# LMAT_AMT_MAG__V1.net
KiCad netlist of a schematic drawn in Altium Designer
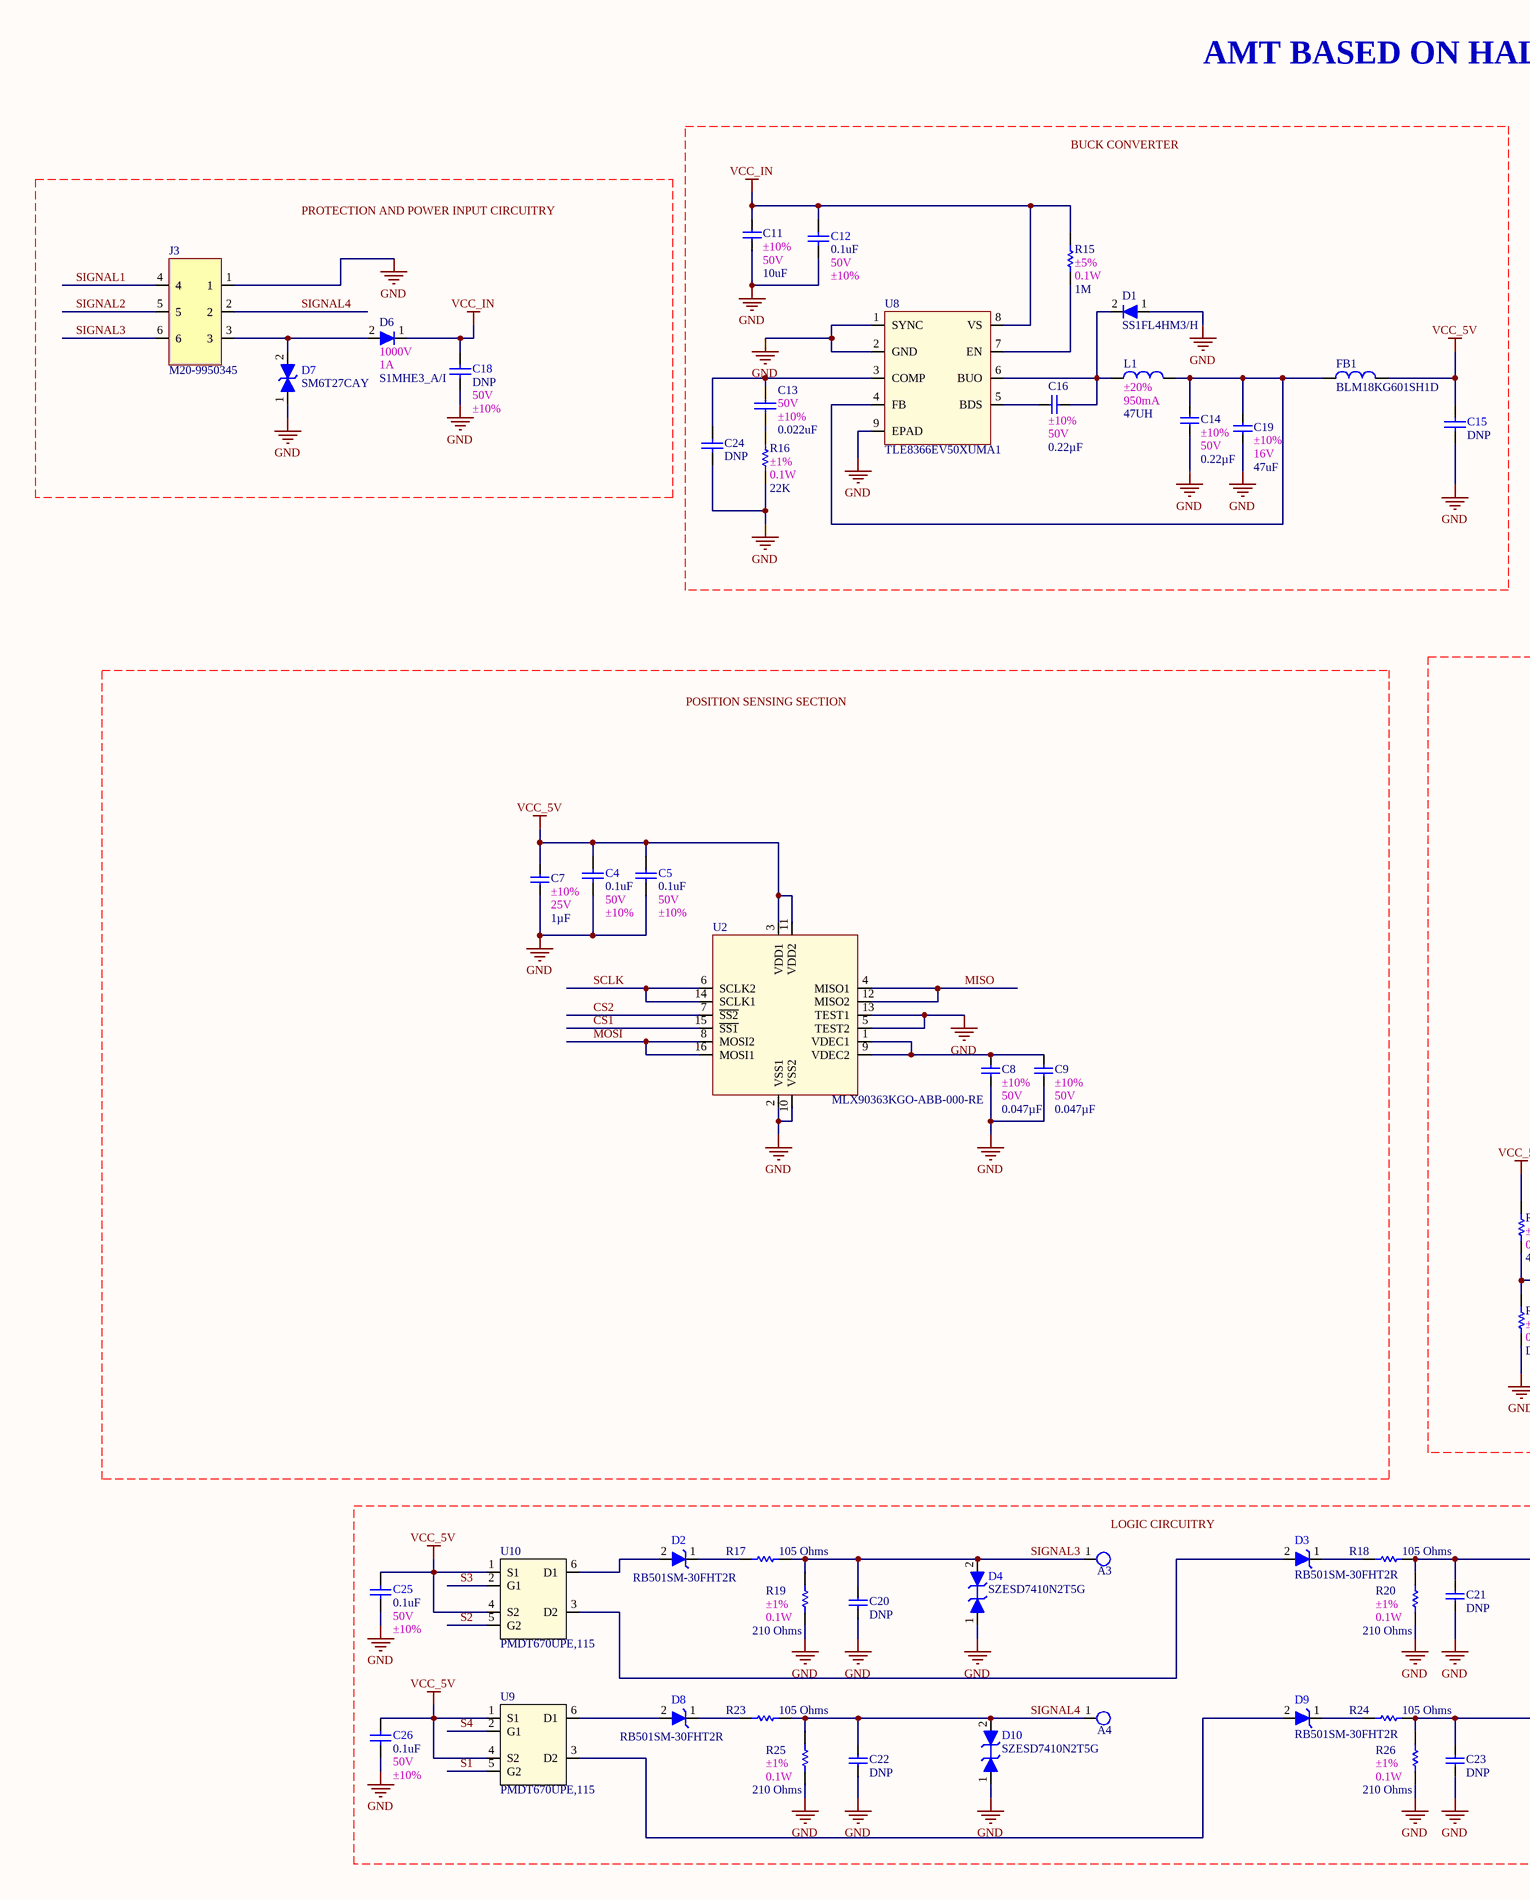
[diagram p0: LMAT_AMT_MAG__V1.SchDoc, left]
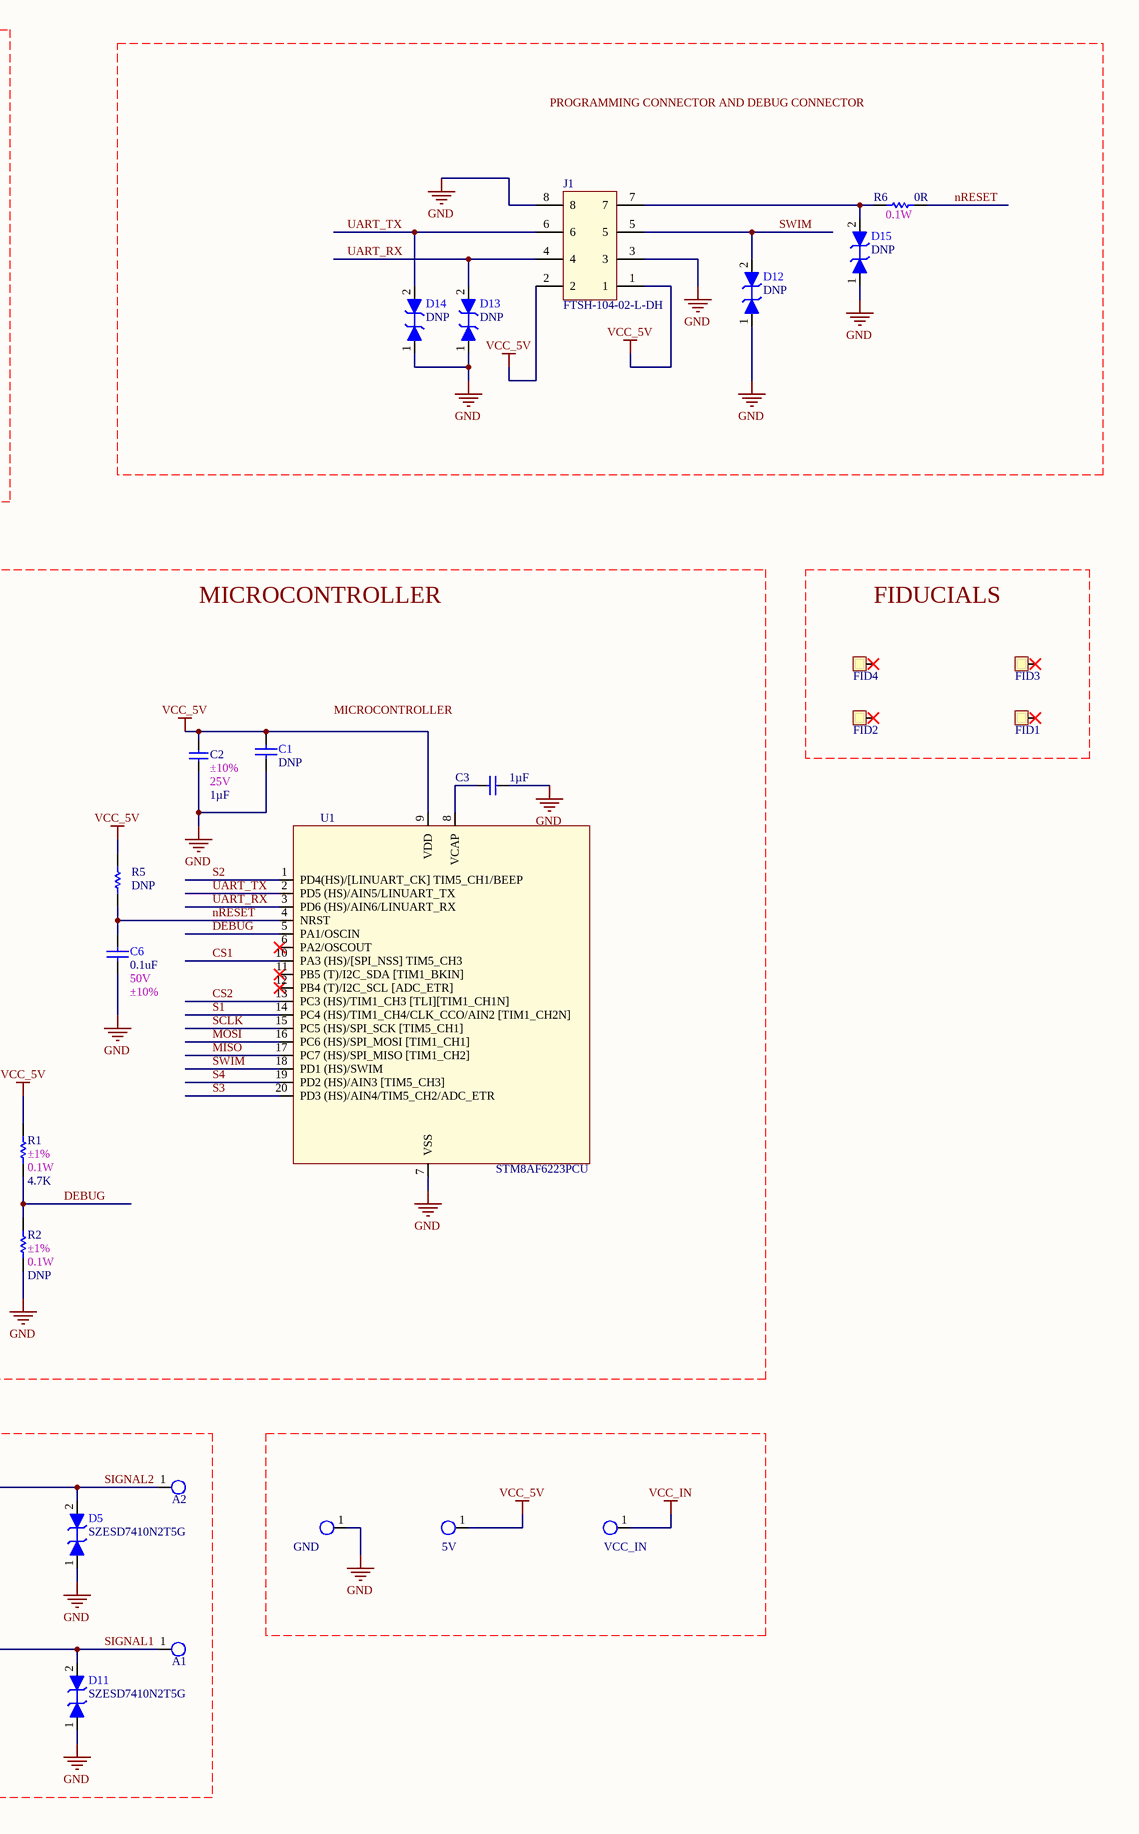
[diagram p1: LMAT_AMT_MAG__V1.SchDoc, right]

(export (version "E")
  (design (tool "Eeschema 10.0.6"))
  (components
    (comp (ref "5V")
      (value "Test Point- 35mil")
      (footprint "TP_35M_DIA")
      (fields (field (name "INTERNAL PART NUMBER") "EMS-TP35MIL-S"))
      (libsource (lib "Integrated_Master_Library") (part "EMS-TP35MIL-S"))
    )
    (comp (ref "A1")
      (value "Test Point- 35mil")
      (footprint "TP_35M_DIA")
      (fields (field (name "INTERNAL PART NUMBER") "EMS-TP35MIL-S"))
      (libsource (lib "Integrated_Master_Library") (part "EMS-TP35MIL-S"))
    )
    (comp (ref "A2")
      (value "Test Point- 35mil")
      (footprint "TP_35M_DIA")
      (fields (field (name "INTERNAL PART NUMBER") "EMS-TP35MIL-S"))
      (libsource (lib "Integrated_Master_Library") (part "EMS-TP35MIL-S"))
    )
    (comp (ref "A3")
      (value "Test Point- 35mil")
      (footprint "TP_35M_DIA")
      (fields (field (name "INTERNAL PART NUMBER") "EMS-TP35MIL-S"))
      (libsource (lib "Integrated_Master_Library") (part "EMS-TP35MIL-S"))
    )
    (comp (ref "A4")
      (value "Test Point- 35mil")
      (footprint "TP_35M_DIA")
      (fields (field (name "INTERNAL PART NUMBER") "EMS-TP35MIL-S"))
      (libsource (lib "Integrated_Master_Library") (part "EMS-TP35MIL-S"))
    )
    (comp (ref "C1")
      (value "DNP")
      (footprint "SMDC0603")
      (description "CAP CER 0.1UF 50V 10% X7R 0603")
      (fields
        (field (name "MANUFACTURER PART NUMBER") "CGA3E2X7R1H104K080AA")
        (field (name "MANUFACTURER") "TDK Corporation")
      )
      (libsource (lib "Integrated_Master_Library") (part "ECA0U10K50V0-SC"))
    )
    (comp (ref "C2")
      (value "1µF")
      (footprint "SMDC0603")
      (description "CAP CER 1UF 25V X7R 0603")
      (fields
        (field (name "MANUFACTURER") "TDK Corporation")
        (field (name "VENDOR PART NUMBER") "445-173628-1-ND")
        (field (name "2ND AUXILIARY FIELD") "±10%")
        (field (name "1ST AUXILIARY FIELD") "25V")
      )
      (libsource (lib "Integrated_Master_Library (3)") (part "ECA1U00L25V0-SC"))
    )
    (comp (ref "C3")
      (value "1µF")
      (footprint "SMDC0603")
      (description "CAP CER 1UF 25V X7R 0603")
      (fields
        (field (name "MANUFACTURER") "TDK Corporation")
        (field (name "VENDOR PART NUMBER") "445-173628-1-ND")
      )
      (libsource (lib "Integrated_Master_Library (3)") (part "ECA1U00L25V0-SC"))
    )
    (comp (ref "C4")
      (value "0.1uF")
      (footprint "SMDC0603")
      (description "CAP CER 0.1UF 50V 10% X7R 0603")
      (fields
        (field (name "MANUFACTURER PART NUMBER") "CGA3E2X7R1H104K080AA")
        (field (name "MANUFACTURER") "TDK Corporation")
        (field (name "1ST AUXILIARY FIELD") "50V")
        (field (name "2ND AUXILIARY FIELD") "±10%")
      )
      (libsource (lib "Integrated_Master_Library") (part "ECA0U10K50V0-SC"))
    )
    (comp (ref "C5")
      (value "0.1uF")
      (footprint "SMDC0603")
      (description "CAP CER 0.1UF 50V 10% X7R 0603")
      (fields
        (field (name "MANUFACTURER PART NUMBER") "CGA3E2X7R1H104K080AA")
        (field (name "MANUFACTURER") "TDK Corporation")
        (field (name "1ST AUXILIARY FIELD") "50V")
        (field (name "2ND AUXILIARY FIELD") "±10%")
      )
      (libsource (lib "Integrated_Master_Library") (part "ECA0U10K50V0-SC"))
    )
    (comp (ref "C6")
      (value "0.1uF")
      (footprint "SMDC0603")
      (description "CAP CER 0.1UF 50V 10% X7R 0603")
      (fields
        (field (name "MANUFACTURER PART NUMBER") "CGA3E2X7R1H104K080AA")
        (field (name "MANUFACTURER") "TDK Corporation")
        (field (name "1ST AUXILIARY FIELD") "50V")
        (field (name "2ND AUXILIARY FIELD") "±10%")
      )
      (libsource (lib "Integrated_Master_Library") (part "ECA0U10K50V0-SC"))
    )
    (comp (ref "C7")
      (value "1µF")
      (footprint "SMDC0603")
      (description "CAP CER 1UF 25V X7R 0603")
      (fields
        (field (name "MANUFACTURER") "TDK Corporation")
        (field (name "VENDOR PART NUMBER") "445-173628-1-ND")
        (field (name "2ND AUXILIARY FIELD") "±10%")
        (field (name "1ST AUXILIARY FIELD") "25V")
      )
      (libsource (lib "Integrated_Master_Library (3)") (part "ECA1U00L25V0-SC"))
    )
    (comp (ref "C8")
      (value "0.047µF")
      (footprint "SMDC0603")
      (description "CAP CER 0.047UF 50V X7R 0603")
      (fields
        (field (name "MANUFACTURER") "TDK Corporation")
        (field (name "VENDOR PART NUMBER") "445-5664-1-ND")
        (field (name "2ND AUXILIARY FIELD") "±10%")
        (field (name "1ST AUXILIARY FIELD") "50V")
      )
      (libsource (lib "Integrated_Master_Library") (part "ECA47N0L50V-SC"))
    )
    (comp (ref "C9")
      (value "0.047µF")
      (footprint "SMDC0603")
      (description "CAP CER 0.047UF 50V X7R 0603")
      (fields
        (field (name "MANUFACTURER") "TDK Corporation")
        (field (name "VENDOR PART NUMBER") "445-5664-1-ND")
        (field (name "2ND AUXILIARY FIELD") "±10%")
        (field (name "1ST AUXILIARY FIELD") "50V")
      )
      (libsource (lib "Integrated_Master_Library") (part "ECA47N0L50V-SC"))
    )
    (comp (ref "C11")
      (value "10uF")
      (footprint "SMDC1210")
      (description "CAP CER 10UF 50V X7R 1210")
      (fields
        (field (name "MANUFACTURER") "Taiyo Yuden")
        (field (name "VENDOR PART NUMBER") "587-6026-1-ND")
        (field (name "2ND AUXILIARY FIELD") "±10%")
        (field (name "1ST AUXILIARY FIELD") "50V")
      )
      (libsource (lib "AMT") (part "ECA10U0L50V0-SH"))
    )
    (comp (ref "C12")
      (value "0.1uF")
      (footprint "SMDC0603")
      (description "CAP CER 0.1UF 50V 10% X7R 0603")
      (fields
        (field (name "MANUFACTURER PART NUMBER") "CGA3E2X7R1H104K080AA")
        (field (name "MANUFACTURER") "TDK Corporation")
        (field (name "1ST AUXILIARY FIELD") "50V")
        (field (name "2ND AUXILIARY FIELD") "±10%")
      )
      (libsource (lib "Integrated_Master_Library") (part "ECA0U10K50V0-SC"))
    )
    (comp (ref "C13")
      (value "0.022uF")
      (footprint "SMDC0603")
      (description "CAP CER 0.022UF 50V 10% X7R 0603")
      (fields
        (field (name "MANUFACTURER PART NUMBER") "CGA3E2X7R1H223K080AA")
        (field (name "MANUFACTURER") "TDK Corporation")
        (field (name "1ST AUXILIARY FIELD") "50V")
        (field (name "2ND AUXILIARY FIELD") "±10%")
      )
      (libsource (lib "Integrated_Master_Library") (part "ECA0U022K50V0-SC"))
    )
    (comp (ref "C14")
      (value "0.22µF")
      (footprint "Automobile-ML:SMDC0603")
      (description "CAP CER 0.22UF 50V X7R 0603")
      (fields
        (field (name "MANUFACTURER") "Murata Electronics North America")
        (field (name "VENDOR PART NUMBER") "490-14410-1-ND")
        (field (name "2ND AUXILIARY FIELD") "±10%")
        (field (name "1ST AUXILIARY FIELD") "50V")
      )
      (libsource (lib "Integrated_Master_Library (3)") (part "ECA0U22L50V0-SC"))
    )
    (comp (ref "C15")
      (value "DNP")
      (footprint "SMDC0603")
      (description "CAP CER 0.1UF 50V 10% X7R 0603")
      (fields
        (field (name "MANUFACTURER PART NUMBER") "CGA3E2X7R1H104K080AA")
        (field (name "MANUFACTURER") "TDK Corporation")
      )
      (libsource (lib "Integrated_Master_Library") (part "ECA0U10K50V0-SC"))
    )
    (comp (ref "C16")
      (value "0.22µF")
      (footprint "SMDC0603")
      (description "CAP CER 0.22UF 50V X7R 0603")
      (fields
        (field (name "MANUFACTURER") "Murata Electronics North America")
        (field (name "VENDOR PART NUMBER") "490-14410-1-ND")
        (field (name "2ND AUXILIARY FIELD") "±10%")
        (field (name "1ST AUXILIARY FIELD") "50V")
      )
      (libsource (lib "Integrated_Master_Library") (part "ECA0U22L50V0-SC"))
    )
    (comp (ref "C18")
      (value "DNP")
      (footprint "SMDC0603")
      (description "CAP CER 0.1UF 50V 10% X7R 0603")
      (fields
        (field (name "MANUFACTURER PART NUMBER") "CGA3E2X7R1H104K080AA")
        (field (name "MANUFACTURER") "TDK Corporation")
        (field (name "1ST AUXILIARY FIELD") "50V")
        (field (name "2ND AUXILIARY FIELD") "±10%")
      )
      (libsource (lib "Integrated_Master_Library") (part "ECA0U10K50V0-SC"))
    )
    (comp (ref "C19")
      (value "47uF")
      (footprint "SMDC1210")
      (description "CAP CER 47UF 16V X6S 1210")
      (fields
        (field (name "MANUFACTURER") "Murata Electronics North America")
        (field (name "VENDOR PART NUMBER") "490-12494-1-ND")
        (field (name "2ND AUXILIARY FIELD") "±10%")
        (field (name "1ST AUXILIARY FIELD") "16V")
      )
      (libsource (lib "Automobile-ML") (part "ECA47U0L16V0-SH"))
    )
    (comp (ref "C20")
      (value "DNP")
      (footprint "SMDC0603")
      (description "CAP CER 10000PF 50V X8R 0603")
      (fields
        (field (name "MANUFACTURER") "TDK Corporation")
        (field (name "VENDOR PART NUMBER") "445-5892-1-ND")
      )
      (libsource (lib "Automobile-ML") (part "ECA0U01L50V0-SC"))
    )
    (comp (ref "C21")
      (value "DNP")
      (footprint "SMDC0603")
      (description "CAP CER 10000PF 50V X8R 0603")
      (fields
        (field (name "MANUFACTURER") "TDK Corporation")
        (field (name "VENDOR PART NUMBER") "445-5892-1-ND")
      )
      (libsource (lib "Automobile-ML") (part "ECA0U01L50V0-SC"))
    )
    (comp (ref "C22")
      (value "DNP")
      (footprint "SMDC0603")
      (description "CAP CER 10000PF 50V X8R 0603")
      (fields
        (field (name "MANUFACTURER") "TDK Corporation")
        (field (name "VENDOR PART NUMBER") "445-5892-1-ND")
      )
      (libsource (lib "Automobile-ML") (part "ECA0U01L50V0-SC"))
    )
    (comp (ref "C23")
      (value "DNP")
      (footprint "SMDC0603")
      (description "CAP CER 10000PF 50V X8R 0603")
      (fields
        (field (name "MANUFACTURER") "TDK Corporation")
        (field (name "VENDOR PART NUMBER") "445-5892-1-ND")
      )
      (libsource (lib "Automobile-ML") (part "ECA0U01L50V0-SC"))
    )
    (comp (ref "C24")
      (value "DNP")
      (footprint "SMDC0603")
      (description "CAP CER 0.022UF 50V 10% X7R 0603")
      (fields
        (field (name "MANUFACTURER PART NUMBER") "CGA3E2X7R1H223K080AA")
        (field (name "MANUFACTURER") "TDK Corporation")
      )
      (libsource (lib "Integrated_Master_Library") (part "ECA0U022K50V0-SC"))
    )
    (comp (ref "C25")
      (value "0.1uF")
      (footprint "SMDC0603")
      (description "CAP CER 0.1UF 50V 10% X7R 0603")
      (fields
        (field (name "MANUFACTURER PART NUMBER") "CGA3E2X7R1H104K080AA")
        (field (name "MANUFACTURER") "TDK Corporation")
        (field (name "1ST AUXILIARY FIELD") "50V")
        (field (name "2ND AUXILIARY FIELD") "±10%")
      )
      (libsource (lib "Integrated_Master_Library") (part "ECA0U10K50V0-SC"))
    )
    (comp (ref "C26")
      (value "0.1uF")
      (footprint "SMDC0603")
      (description "CAP CER 0.1UF 50V 10% X7R 0603")
      (fields
        (field (name "MANUFACTURER PART NUMBER") "CGA3E2X7R1H104K080AA")
        (field (name "MANUFACTURER") "TDK Corporation")
        (field (name "1ST AUXILIARY FIELD") "50V")
        (field (name "2ND AUXILIARY FIELD") "±10%")
      )
      (libsource (lib "Integrated_Master_Library") (part "ECA0U10K50V0-SC"))
    )
    (comp (ref "D1")
      (value "SS1FL4HM3/H")
      (footprint "Integrated_Master_Library:SODFL370X110-2N")
      (description "DIODE SCHOTTKY 40V 1A DO-219AB")
      (fields
        (field (name "MANUFACTURER") "Vishay Semiconductor Diodes Division")
        (field (name "INTERNAL PART NUMBER") "EDDVS1A0040V0-S")
      )
      (libsource (lib "Integrated_Master_Library (3)") (part "EDDVS1A0040V0-S"))
    )
    (comp (ref "D2")
      (value "RB501SM-30FHT2R")
      (footprint "SOD1700X70N-V2")
      (description "Diode Schottky 30V 100mA Surface Mount EMD2")
      (fields
        (field (name "MANUFACTURER") "Rohm Semiconductor")
        (field (name "INTERNAL PART NUMBER") "EDDR0A1030V0-S")
      )
      (libsource (lib "Integrated_Master_Library (3)") (part "EDDR0A1030V0-S"))
    )
    (comp (ref "D3")
      (value "RB501SM-30FHT2R")
      (footprint "SOD1700X70N-V2")
      (description "Diode Schottky 30V 100mA Surface Mount EMD2")
      (fields
        (field (name "MANUFACTURER") "Rohm Semiconductor")
        (field (name "INTERNAL PART NUMBER") "EDDR0A1030V0-S")
      )
      (libsource (lib "Integrated_Master_Library (3)") (part "EDDR0A1030V0-S"))
    )
    (comp (ref "D4")
      (value "SZESD7410N2T5G")
      (footprint "DFN65P100X65X45-2N")
      (description "TVS DIODE 8V 20V 2X2DFN")
      (fields
        (field (name "MANUFACTURER") "ON Semiconductor")
        (field (name "INTERNAL PART NUMBER") "EDDOS16A010V0-S")
      )
      (libsource (lib "Automobile-ML") (part "EDDOS16A010V0-S"))
    )
    (comp (ref "D5")
      (value "SZESD7410N2T5G")
      (footprint "DFN65P100X65X45-2N")
      (description "TVS DIODE 8V 20V 2X2DFN")
      (fields
        (field (name "MANUFACTURER") "ON Semiconductor")
        (field (name "INTERNAL PART NUMBER") "EDDOS16A010V0-S")
      )
      (libsource (lib "Automobile-ML") (part "EDDOS16A010V0-S"))
    )
    (comp (ref "D6")
      (value "S1MHE3_A/I")
      (footprint "DIOM4227X23N-2N")
      (description "DIODE GEN PURP 1KV 1A DO214AC")
      (fields
        (field (name "MANUFACTURER") "Vishay Semiconductor Diodes Division")
        (field (name "INTERNAL PART NUMBER") "EDDVS1A001000V-S")
        (field (name "1ST AUXILIARY FIELD") "1000V")
        (field (name "2ND AUXILIARY FIELD") "1A")
      )
      (libsource (lib "Integrated_Master_Library") (part "EDDVS1A001000V-S"))
    )
    (comp (ref "D7")
      (value "SM6T27CAY")
      (footprint "DIOM4336X26B")
      (description "TVS DIODE 23.1V 48.3V SMB")
      (fields
        (field (name "MANUFACTURER") "STMicroelectronics")
        (field (name "INTERNAL PART NUMBER") "EDDST83A025V7-S")
      )
      (libsource (lib "Integrated_Master_Library") (part "EDDST83A025V7-S"))
    )
    (comp (ref "D8")
      (value "RB501SM-30FHT2R")
      (footprint "SOD1700X70N-V2")
      (description "Diode Schottky 30V 100mA Surface Mount EMD2")
      (fields
        (field (name "MANUFACTURER") "Rohm Semiconductor")
        (field (name "INTERNAL PART NUMBER") "EDDR0A1030V0-S")
      )
      (libsource (lib "Integrated_Master_Library (3)") (part "EDDR0A1030V0-S"))
    )
    (comp (ref "D9")
      (value "RB501SM-30FHT2R")
      (footprint "SOD1700X70N-V2")
      (description "Diode Schottky 30V 100mA Surface Mount EMD2")
      (fields
        (field (name "MANUFACTURER") "Rohm Semiconductor")
        (field (name "INTERNAL PART NUMBER") "EDDR0A1030V0-S")
      )
      (libsource (lib "Integrated_Master_Library (3)") (part "EDDR0A1030V0-S"))
    )
    (comp (ref "D10")
      (value "SZESD7410N2T5G")
      (footprint "DFN65P100X65X45-2N")
      (description "TVS DIODE 8V 20V 2X2DFN")
      (fields
        (field (name "MANUFACTURER") "ON Semiconductor")
        (field (name "INTERNAL PART NUMBER") "EDDOS16A010V0-S")
      )
      (libsource (lib "Automobile-ML") (part "EDDOS16A010V0-S"))
    )
    (comp (ref "D11")
      (value "SZESD7410N2T5G")
      (footprint "DFN65P100X65X45-2N")
      (description "TVS DIODE 8V 20V 2X2DFN")
      (fields
        (field (name "MANUFACTURER") "ON Semiconductor")
        (field (name "INTERNAL PART NUMBER") "EDDOS16A010V0-S")
      )
      (libsource (lib "Automobile-ML") (part "EDDOS16A010V0-S"))
    )
    (comp (ref "D12")
      (value "DNP")
      (footprint "DFN65P100X65X45-2N")
      (description "TVS DIODE 8V 20V 2X2DFN")
      (fields
        (field (name "MANUFACTURER PART NUMBER") "SZESD7410N2T5G")
        (field (name "MANUFACTURER") "ON Semiconductor")
      )
      (libsource (lib "Automobile-ML") (part "EDDOS16A010V0-S"))
    )
    (comp (ref "D13")
      (value "DNP")
      (footprint "DFN65P100X65X45-2N")
      (description "TVS DIODE 8V 20V 2X2DFN")
      (fields
        (field (name "MANUFACTURER PART NUMBER") "SZESD7410N2T5G")
        (field (name "MANUFACTURER") "ON Semiconductor")
      )
      (libsource (lib "Automobile-ML") (part "EDDOS16A010V0-S"))
    )
    (comp (ref "D14")
      (value "DNP")
      (footprint "DFN65P100X65X45-2N")
      (description "TVS DIODE 8V 20V 2X2DFN")
      (fields
        (field (name "MANUFACTURER PART NUMBER") "SZESD7410N2T5G")
        (field (name "MANUFACTURER") "ON Semiconductor")
      )
      (libsource (lib "Automobile-ML") (part "EDDOS16A010V0-S"))
    )
    (comp (ref "D15")
      (value "DNP")
      (footprint "DFN65P100X65X45-2N")
      (description "TVS DIODE 8V 20V 2X2DFN")
      (fields
        (field (name "MANUFACTURER PART NUMBER") "SZESD7410N2T5G")
        (field (name "MANUFACTURER") "ON Semiconductor")
      )
      (libsource (lib "Automobile-ML") (part "EDDOS16A010V0-S"))
    )
    (comp (ref "FB1")
      (value "BLM18KG601SH1D")
      (footprint "Integrated_Master_Library:SMDL0603")
      (description "FERRITE BEAD 600 OHM 0603 1LN")
      (fields
        (field (name "MANUFACTURER") "Murata Electronics North America")
        (field (name "VENDOR PART NUMBER") "490-13259-1-ND")
      )
      (libsource (lib "Automobile-ML") (part "EIN600R1A30-S"))
    )
    (comp (ref "FID1")
      (value "FID40X40")
      (footprint "FID40X40")
      (libsource (lib "Integrated_Master_Library") (part "FID_40X40"))
    )
    (comp (ref "FID2")
      (value "FID40X40")
      (footprint "FID40X40")
      (libsource (lib "Integrated_Master_Library") (part "FID_40X40"))
    )
    (comp (ref "FID3")
      (value "FID40X40")
      (footprint "FID40X40")
      (libsource (lib "Integrated_Master_Library") (part "FID_40X40"))
    )
    (comp (ref "FID4")
      (value "FID40X40")
      (footprint "FID40X40")
      (libsource (lib "Integrated_Master_Library") (part "FID_40X40"))
    )
    (comp (ref "GND")
      (value "Test Point- 35mil")
      (footprint "TP_35M_DIA")
      (fields (field (name "INTERNAL PART NUMBER") "EMS-TP35MIL-S"))
      (libsource (lib "Integrated_Master_Library") (part "EMS-TP35MIL-S"))
    )
    (comp (ref "J1")
      (value "CONN HEADER R/A 6POS 2.54MMCONN HEADER SMD R/A 8POS 1.27MM")
      (footprint "HDRRA8W53P127_2X4_9754X251X343P")
      (description "CONN HEADER SMD R/A 8POS 1.27MM")
      (fields
        (field (name "MANUFACTURER") "Samtec Inc.")
        (field (name "INTERNAL PART NUMBER") "ECN-FTSH-104-02-L-DH-0005")
        (field (name "MANUFACTURER PART NUMBER") "FTSH-104-02-L-DH")
      )
      (libsource (lib "Automobile-ML") (part "ECN-FTSH-104-02-L-DH-0005"))
    )
    (comp (ref "J3")
      (value "CONN HEADER R/A 6POS 2.54MM")
      (footprint "HDRRA6W86P254_2X3_1344X254X528P")
      (fields
        (field (name "MANUFACTURER") "Harwin Inc.")
        (field (name "INTERNAL PART NUMBER") "ECN-M20-9950345-0003")
        (field (name "VENDOR PART NUMBER") "952-2092-ND")
        (field (name "MANUFACTURER PART NUMBER") "M20-9950345")
      )
      (libsource (lib "Automobile-ML") (part "ECN-M20-9950345-0003"))
    )
    (comp (ref "L1")
      (value "47UH")
      (footprint "INDC4949X310N")
      (description "FIXED IND 47UH 700MA 422.5 MOHM")
      (fields
        (field (name "MANUFACTURER") "Taiyo Yuden")
        (field (name "VENDOR PART NUMBER") "587-3604-1-ND")
        (field (name "2ND AUXILIARY FIELD") "±20%")
        (field (name "1ST AUXILIARY FIELD") "950mA")
      )
      (libsource (lib "AMT") (part "EIN47U0N950M-S"))
    )
    (comp (ref "R1")
      (value "4.7K")
      (footprint "SMDR0402")
      (description "RES SMD 4.7K OHM 1% 1/10W 0402")
      (fields
        (field (name "MANUFACTURER") "Panasonic Electronic Components")
        (field (name "VENDOR PART NUMBER") "P4.70KLCT-ND")
        (field (name "2ND AUXILIARY FIELD") "±1%")
        (field (name "1ST AUXILIARY FIELD") "0.1W")
      )
      (libsource (lib "Automobile-ML") (part "ERE4K70G110-SB"))
    )
    (comp (ref "R2")
      (value "DNP")
      (footprint "SMDR0402")
      (description "RES SMD 4.7K OHM 1% 1/10W 0402")
      (fields
        (field (name "MANUFACTURER") "Panasonic Electronic Components")
        (field (name "VENDOR PART NUMBER") "P4.70KLCT-ND")
        (field (name "2ND AUXILIARY FIELD") "±1%")
        (field (name "1ST AUXILIARY FIELD") "0.1W")
      )
      (libsource (lib "Automobile-ML") (part "ERE4K70G110-SB"))
    )
    (comp (ref "R5")
      (value "DNP")
      (footprint "SMDR0603")
      (description "RES SMD 47K OHM 1% 1/10W 0603")
      (fields (field (name "MANUFACTURER") "Yageo") (field (name "VENDOR PART NUMBER") "YAG2129CT-ND"))
      (libsource (lib "Integrated_Master_Library (3)") (part "ERE47K0G110-SC"))
    )
    (comp (ref "R6")
      (value "0R")
      (footprint "SMDR0603")
      (description "RES SMD 0.0OHM JUMPER 1/10W 0603")
      (fields
        (field (name "MANUFACTURER PART NUMBER") "ERJ-3GEY0R00V")
        (field (name "MANUFACTURER") "Panasonic Electronic Components")
        (field (name "1ST AUXILIARY FIELD") "0.1W")
      )
      (libsource (lib "Integrated_Master_Library") (part "ERE0R00110-SC"))
    )
    (comp (ref "R15")
      (value "1M")
      (footprint "SMDR0603")
      (description "RES SMD 1M OHM 5% 1/10W 0603")
      (fields
        (field (name "MANUFACTURER") "Vishay Dale")
        (field (name "VENDOR PART NUMBER") "541-2216-1-ND")
        (field (name "2ND AUXILIARY FIELD") "±5%")
        (field (name "1ST AUXILIARY FIELD") "0.1W")
      )
      (libsource (lib "Automobile-ML") (part "ERE1M00K110-SC"))
    )
    (comp (ref "R16")
      (value "22K")
      (footprint "SMDR0603")
      (description "RES SMD 22K OHM 1% 1/10W 0603")
      (fields
        (field (name "MANUFACTURER") "Panasonic Electronic Components")
        (field (name "VENDOR PART NUMBER") "P22.0KHCT-ND")
        (field (name "2ND AUXILIARY FIELD") "±1%")
        (field (name "1ST AUXILIARY FIELD") "0.1W")
      )
      (libsource (lib "Automobile-ML") (part "ERE22K0G110-SC"))
    )
    (comp (ref "R17")
      (value "105 Ohms")
      (footprint "SMDR0603")
      (description "RES SMD 105 OHM 1% 1/10W 0603")
      (fields
        (field (name "MANUFACTURER") "Panasonic Electronic Components")
        (field (name "VENDOR PART NUMBER") "P105HCT-ND")
      )
      (libsource (lib "Automobile-ML") (part "ERE105RG110-SC"))
    )
    (comp (ref "R18")
      (value "105 Ohms")
      (footprint "SMDR0603")
      (description "RES SMD 105 OHM 1% 1/10W 0603")
      (fields
        (field (name "MANUFACTURER") "Panasonic Electronic Components")
        (field (name "VENDOR PART NUMBER") "P105HCT-ND")
      )
      (libsource (lib "Automobile-ML") (part "ERE105RG110-SC"))
    )
    (comp (ref "R19")
      (value "210 Ohms")
      (footprint "SMDR0603")
      (description "RES SMD 210 OHM 1% 1/10W 0603")
      (fields
        (field (name "MANUFACTURER") "Panasonic Electronic Components")
        (field (name "VENDOR PART NUMBER") "P210HCT-ND")
        (field (name "2ND AUXILIARY FIELD") "±1%")
        (field (name "1ST AUXILIARY FIELD") "0.1W")
      )
      (libsource (lib "Automobile-ML") (part "ERE210RG110-SC"))
    )
    (comp (ref "R20")
      (value "210 Ohms")
      (footprint "SMDR0603")
      (description "RES SMD 210 OHM 1% 1/10W 0603")
      (fields
        (field (name "MANUFACTURER") "Panasonic Electronic Components")
        (field (name "VENDOR PART NUMBER") "P210HCT-ND")
        (field (name "2ND AUXILIARY FIELD") "±1%")
        (field (name "1ST AUXILIARY FIELD") "0.1W")
      )
      (libsource (lib "Automobile-ML") (part "ERE210RG110-SC"))
    )
    (comp (ref "R23")
      (value "105 Ohms")
      (footprint "SMDR0603")
      (description "RES SMD 105 OHM 1% 1/10W 0603")
      (fields
        (field (name "MANUFACTURER") "Panasonic Electronic Components")
        (field (name "VENDOR PART NUMBER") "P105HCT-ND")
      )
      (libsource (lib "Automobile-ML") (part "ERE105RG110-SC"))
    )
    (comp (ref "R24")
      (value "105 Ohms")
      (footprint "SMDR0603")
      (description "RES SMD 105 OHM 1% 1/10W 0603")
      (fields
        (field (name "MANUFACTURER") "Panasonic Electronic Components")
        (field (name "VENDOR PART NUMBER") "P105HCT-ND")
      )
      (libsource (lib "Automobile-ML") (part "ERE105RG110-SC"))
    )
    (comp (ref "R25")
      (value "210 Ohms")
      (footprint "SMDR0603")
      (description "RES SMD 210 OHM 1% 1/10W 0603")
      (fields
        (field (name "MANUFACTURER") "Panasonic Electronic Components")
        (field (name "VENDOR PART NUMBER") "P210HCT-ND")
        (field (name "2ND AUXILIARY FIELD") "±1%")
        (field (name "1ST AUXILIARY FIELD") "0.1W")
      )
      (libsource (lib "Automobile-ML") (part "ERE210RG110-SC"))
    )
    (comp (ref "R26")
      (value "210 Ohms")
      (footprint "SMDR0603")
      (description "RES SMD 210 OHM 1% 1/10W 0603")
      (fields
        (field (name "MANUFACTURER") "Panasonic Electronic Components")
        (field (name "VENDOR PART NUMBER") "P210HCT-ND")
        (field (name "2ND AUXILIARY FIELD") "±1%")
        (field (name "1ST AUXILIARY FIELD") "0.1W")
      )
      (libsource (lib "Automobile-ML") (part "ERE210RG110-SC"))
    )
    (comp (ref "U1")
      (value "STM8AF6223PCU")
      (footprint "SOP65P640X120-20N")
      (description "IC MCU 8BIT 8KB FLASH 20TSSOP")
      (fields
        (field (name "MANUFACTURER") "STMicroelectronics")
        (field (name "INTERNAL PART NUMBER") "EICSTMTSSOP-20-1691")
      )
      (libsource (lib "Integrated_Master_Library (3)") (part "EICSTMTSSOP-20-1691"))
    )
    (comp (ref "U2")
      (value "MLX90363KGO-ABB-000-RE")
      (footprint "SOP65P640X120-16N")
      (description "SENSOR HALL EFFECT SPI 16TSSOP")
      (fields
        (field (name "MANUFACTURER") "Melexis Technologies NV")
        (field (name "INTERNAL PART NUMBER") "EICMTTSSOP-16-1690")
      )
      (libsource (lib "Integrated_Master_Library") (part "EICMTTSSOP-16-1690"))
    )
    (comp (ref "U8")
      (value "TLE8366EV50XUMA1")
      (footprint "SOIC127P600X170_HS-9N")
      (description "IC REG BUCK 5V 1.8A 8DSO")
      (fields
        (field (name "MANUFACTURER") "Infineon Technologies")
        (field (name "INTERNAL PART NUMBER") "EICITSOIC-08-0001")
      )
      (libsource (lib "Automobile-ML") (part "EICITSOIC-08-0001"))
    )
    (comp (ref "U9")
      (value "PMDT670UPE,115")
      (footprint "SOTFL50P160X60-6N")
      (description "MOSFET 2P-CH 20V 0.55A SOT666")
      (fields
        (field (name "MANUFACTURER") "Nexperia USA Inc.")
        (field (name "INTERNAL PART NUMBER") "EICNUSOT666-06-0004")
      )
      (libsource (lib "Automobile-ML") (part "EICNUSOT666-06-0004"))
    )
    (comp (ref "U10")
      (value "PMDT670UPE,115")
      (footprint "SOTFL50P160X60-6N")
      (description "MOSFET 2P-CH 20V 0.55A SOT666")
      (fields
        (field (name "MANUFACTURER") "Nexperia USA Inc.")
        (field (name "INTERNAL PART NUMBER") "EICNUSOT666-06-0004")
      )
      (libsource (lib "Automobile-ML") (part "EICNUSOT666-06-0004"))
    )
    (comp (ref "VCC_IN")
      (value "Test Point- 35mil")
      (footprint "TP_35M_DIA")
      (fields (field (name "INTERNAL PART NUMBER") "EMS-TP35MIL-S"))
      (libsource (lib "Integrated_Master_Library") (part "EMS-TP35MIL-S"))
    )
  )
  (nets
    (net (code "1") (name "/CS1") (class "Default")
      (node (ref "U1") (pin "10") (pinfunction "PA3_(HS)/[SPI_NSS]_TIM5_CH3_10") (pintype "passive"))
      (node (ref "U2") (pin "15") (pinfunction "~{SS1}_15") (pintype "passive"))
    )
    (net (code "2") (name "/CS2") (class "Default")
      (node (ref "U1") (pin "13") (pinfunction "PC3_(HS)/TIM1_CH3_[TLI][TIM1_CH1N]_13") (pintype "passive"))
      (node (ref "U2") (pin "7") (pinfunction "~{SS2}_7") (pintype "passive"))
    )
    (net (code "3") (name "/DEBUG") (class "Default")
      (node (ref "R1") (pin "1") (pinfunction "1_1") (pintype "passive"))
      (node (ref "R2") (pin "2") (pinfunction "2_2") (pintype "passive"))
      (node (ref "U1") (pin "5") (pinfunction "PA1/OSCIN_5") (pintype "passive"))
    )
    (net (code "4") (name "/MISO") (class "Default")
      (node (ref "U1") (pin "17") (pinfunction "PC7_(HS)/SPI_MISO_[TIM1_CH2]_17") (pintype "passive"))
      (node (ref "U2") (pin "12") (pinfunction "MISO2_12") (pintype "passive"))
      (node (ref "U2") (pin "4") (pinfunction "MISO1_4") (pintype "passive"))
    )
    (net (code "5") (name "/MOSI") (class "Default")
      (node (ref "U1") (pin "16") (pinfunction "PC6_(HS)/SPI_MOSI_[TIM1_CH1]_16") (pintype "passive"))
      (node (ref "U2") (pin "16") (pinfunction "MOSI1_16") (pintype "passive"))
      (node (ref "U2") (pin "8") (pinfunction "MOSI2_8") (pintype "passive"))
    )
    (net (code "6") (name "/S1") (class "Default")
      (node (ref "U1") (pin "14") (pinfunction "PC4_(HS)/TIM1_CH4/CLK_CCO/AIN2_[TIM1_CH2N]_14") (pintype "passive"))
      (node (ref "U9") (pin "5") (pinfunction "G2_5") (pintype "passive"))
    )
    (net (code "7") (name "/S2") (class "Default")
      (node (ref "U1") (pin "1") (pinfunction "PD4(HS)/[LINUART_CK]_TIM5_CH1/BEEP_1") (pintype "passive"))
      (node (ref "U10") (pin "5") (pinfunction "G2_5") (pintype "passive"))
    )
    (net (code "8") (name "/S3") (class "Default")
      (node (ref "U1") (pin "20") (pinfunction "PD3_(HS)/AIN4/TIM5_CH2/ADC_ETR_20") (pintype "passive"))
      (node (ref "U10") (pin "2") (pinfunction "G1_2") (pintype "passive"))
    )
    (net (code "9") (name "/S4") (class "Default")
      (node (ref "U1") (pin "19") (pinfunction "PD2_(HS)/AIN3_[TIM5_CH3]_19") (pintype "passive"))
      (node (ref "U9") (pin "2") (pinfunction "G1_2") (pintype "passive"))
    )
    (net (code "10") (name "/SCLK") (class "Default")
      (node (ref "U1") (pin "15") (pinfunction "PC5_(HS)/SPI_SCK_[TIM5_CH1]_15") (pintype "passive"))
      (node (ref "U2") (pin "14") (pinfunction "SCLK1_14") (pintype "passive"))
      (node (ref "U2") (pin "6") (pinfunction "SCLK2_6") (pintype "passive"))
    )
    (net (code "11") (name "/SIGNAL1") (class "Default")
      (node (ref "A1") (pin "1") (pinfunction "1_1") (pintype "passive"))
      (node (ref "C23") (pin "2") (pinfunction "2_2") (pintype "passive"))
      (node (ref "D11") (pin "2") (pinfunction "CATHODE_2") (pintype "passive"))
      (node (ref "J3") (pin "4") (pinfunction "4_4") (pintype "passive"))
      (node (ref "R24") (pin "2") (pinfunction "2_2") (pintype "passive"))
      (node (ref "R26") (pin "1") (pinfunction "1_1") (pintype "passive"))
    )
    (net (code "12") (name "/SIGNAL2") (class "Default")
      (node (ref "A2") (pin "1") (pinfunction "1_1") (pintype "passive"))
      (node (ref "C21") (pin "2") (pinfunction "2_2") (pintype "passive"))
      (node (ref "D5") (pin "2") (pinfunction "CATHODE_2") (pintype "passive"))
      (node (ref "J3") (pin "5") (pinfunction "5_5") (pintype "passive"))
      (node (ref "R18") (pin "2") (pinfunction "2_2") (pintype "passive"))
      (node (ref "R20") (pin "1") (pinfunction "1_1") (pintype "passive"))
    )
    (net (code "13") (name "/SIGNAL3") (class "Default")
      (node (ref "A3") (pin "1") (pinfunction "1_1") (pintype "passive"))
      (node (ref "C20") (pin "2") (pinfunction "2_2") (pintype "passive"))
      (node (ref "D4") (pin "2") (pinfunction "CATHODE_2") (pintype "passive"))
      (node (ref "J3") (pin "6") (pinfunction "6_6") (pintype "passive"))
      (node (ref "R17") (pin "2") (pinfunction "2_2") (pintype "passive"))
      (node (ref "R19") (pin "1") (pinfunction "1_1") (pintype "passive"))
    )
    (net (code "14") (name "/SIGNAL4") (class "Default")
      (node (ref "A4") (pin "1") (pinfunction "1_1") (pintype "passive"))
      (node (ref "C22") (pin "2") (pinfunction "2_2") (pintype "passive"))
      (node (ref "D10") (pin "2") (pinfunction "CATHODE_2") (pintype "passive"))
      (node (ref "J3") (pin "2") (pinfunction "2_2") (pintype "passive"))
      (node (ref "R23") (pin "2") (pinfunction "2_2") (pintype "passive"))
      (node (ref "R25") (pin "1") (pinfunction "1_1") (pintype "passive"))
    )
    (net (code "15") (name "/SWIM") (class "Default")
      (node (ref "D12") (pin "2") (pinfunction "CATHODE_2") (pintype "passive"))
      (node (ref "J1") (pin "5") (pinfunction "5_5") (pintype "passive"))
      (node (ref "U1") (pin "18") (pinfunction "PD1_(HS)/SWIM_18") (pintype "passive"))
    )
    (net (code "16") (name "/UART_RX") (class "Default")
      (node (ref "D13") (pin "2") (pinfunction "CATHODE_2") (pintype "passive"))
      (node (ref "J1") (pin "4") (pinfunction "4_4") (pintype "passive"))
      (node (ref "U1") (pin "3") (pinfunction "PD6_(HS)/AIN6/LINUART_RX_3") (pintype "passive"))
    )
    (net (code "17") (name "/UART_TX") (class "Default")
      (node (ref "D14") (pin "2") (pinfunction "CATHODE_2") (pintype "passive"))
      (node (ref "J1") (pin "6") (pinfunction "6_6") (pintype "passive"))
      (node (ref "U1") (pin "2") (pinfunction "PD5_(HS)/AIN5/LINUART_TX_2") (pintype "passive"))
    )
    (net (code "18") (name "/nRESET") (class "Default")
      (node (ref "C6") (pin "1") (pinfunction "1_1") (pintype "passive"))
      (node (ref "R5") (pin "1") (pinfunction "1_1") (pintype "passive"))
      (node (ref "R6") (pin "2") (pinfunction "2_2") (pintype "passive"))
      (node (ref "U1") (pin "4") (pinfunction "NRST_4") (pintype "passive"))
    )
    (net (code "19") (name "GND") (class "Default")
      (node (ref "C1") (pin "2") (pinfunction "2_2") (pintype "passive"))
      (node (ref "C11") (pin "1") (pinfunction "1_1") (pintype "passive"))
      (node (ref "C12") (pin "2") (pinfunction "2_2") (pintype "passive"))
      (node (ref "C14") (pin "1") (pinfunction "1_1") (pintype "passive"))
      (node (ref "C15") (pin "2") (pinfunction "2_2") (pintype "passive"))
      (node (ref "C18") (pin "2") (pinfunction "2_2") (pintype "passive"))
      (node (ref "C19") (pin "1") (pinfunction "1_1") (pintype "passive"))
      (node (ref "C2") (pin "1") (pinfunction "1_1") (pintype "passive"))
      (node (ref "C20") (pin "1") (pinfunction "1_1") (pintype "passive"))
      (node (ref "C21") (pin "1") (pinfunction "1_1") (pintype "passive"))
      (node (ref "C22") (pin "1") (pinfunction "1_1") (pintype "passive"))
      (node (ref "C23") (pin "1") (pinfunction "1_1") (pintype "passive"))
      (node (ref "C24") (pin "2") (pinfunction "2_2") (pintype "passive"))
      (node (ref "C25") (pin "2") (pinfunction "2_2") (pintype "passive"))
      (node (ref "C26") (pin "2") (pinfunction "2_2") (pintype "passive"))
      (node (ref "C3") (pin "2") (pinfunction "2_2") (pintype "passive"))
      (node (ref "C4") (pin "2") (pinfunction "2_2") (pintype "passive"))
      (node (ref "C5") (pin "2") (pinfunction "2_2") (pintype "passive"))
      (node (ref "C6") (pin "2") (pinfunction "2_2") (pintype "passive"))
      (node (ref "C7") (pin "1") (pinfunction "1_1") (pintype "passive"))
      (node (ref "C8") (pin "1") (pinfunction "1_1") (pintype "passive"))
      (node (ref "C9") (pin "1") (pinfunction "1_1") (pintype "passive"))
      (node (ref "D1") (pin "1") (pinfunction "Cathode_1") (pintype "passive"))
      (node (ref "D10") (pin "1") (pinfunction "ANODE_1") (pintype "passive"))
      (node (ref "D11") (pin "1") (pinfunction "ANODE_1") (pintype "passive"))
      (node (ref "D12") (pin "1") (pinfunction "ANODE_1") (pintype "passive"))
      (node (ref "D13") (pin "1") (pinfunction "ANODE_1") (pintype "passive"))
      (node (ref "D14") (pin "1") (pinfunction "ANODE_1") (pintype "passive"))
      (node (ref "D15") (pin "1") (pinfunction "ANODE_1") (pintype "passive"))
      (node (ref "D4") (pin "1") (pinfunction "ANODE_1") (pintype "passive"))
      (node (ref "D5") (pin "1") (pinfunction "ANODE_1") (pintype "passive"))
      (node (ref "D7") (pin "1") (pinfunction "ANODE_1") (pintype "passive"))
      (node (ref "GND") (pin "1") (pinfunction "1_1") (pintype "passive"))
      (node (ref "J1") (pin "3") (pinfunction "3_3") (pintype "passive"))
      (node (ref "J1") (pin "8") (pinfunction "8_8") (pintype "passive"))
      (node (ref "J3") (pin "1") (pinfunction "1_1") (pintype "passive"))
      (node (ref "R16") (pin "1") (pinfunction "1_1") (pintype "passive"))
      (node (ref "R19") (pin "2") (pinfunction "2_2") (pintype "passive"))
      (node (ref "R2") (pin "1") (pinfunction "1_1") (pintype "passive"))
      (node (ref "R20") (pin "2") (pinfunction "2_2") (pintype "passive"))
      (node (ref "R25") (pin "2") (pinfunction "2_2") (pintype "passive"))
      (node (ref "R26") (pin "2") (pinfunction "2_2") (pintype "passive"))
      (node (ref "U1") (pin "7") (pinfunction "VSS_7") (pintype "passive"))
      (node (ref "U2") (pin "10") (pinfunction "VSS2_10") (pintype "passive"))
      (node (ref "U2") (pin "13") (pinfunction "TEST1_13") (pintype "passive"))
      (node (ref "U2") (pin "2") (pinfunction "VSS1_2") (pintype "passive"))
      (node (ref "U2") (pin "5") (pinfunction "TEST2_5") (pintype "passive"))
      (node (ref "U8") (pin "1") (pinfunction "SYNC_1") (pintype "passive"))
      (node (ref "U8") (pin "2") (pinfunction "GND_2") (pintype "passive"))
      (node (ref "U8") (pin "9") (pinfunction "EPAD_9") (pintype "passive"))
    )
    (net (code "20") (name "Net-(C13-Pad2)") (class "Default")
      (node (ref "C13") (pin "2") (pinfunction "2_2") (pintype "passive"))
      (node (ref "R16") (pin "2") (pinfunction "2_2") (pintype "passive"))
    )
    (net (code "21") (name "Net-(D1-Anode)") (class "Default")
      (node (ref "C16") (pin "2") (pinfunction "2_2") (pintype "passive"))
      (node (ref "D1") (pin "2") (pinfunction "Anode_2") (pintype "passive"))
      (node (ref "L1") (pin "1") (pinfunction "1_1") (pintype "passive"))
      (node (ref "U8") (pin "6") (pinfunction "BUO_6") (pintype "passive"))
    )
    (net (code "22") (name "Net-(D2-ANODE)") (class "Default")
      (node (ref "D2") (pin "2") (pinfunction "ANODE_2") (pintype "passive"))
      (node (ref "U10") (pin "6") (pinfunction "D1_6") (pintype "passive"))
    )
    (net (code "23") (name "Net-(D2-CATHODE)") (class "Default")
      (node (ref "D2") (pin "1") (pinfunction "CATHODE_1") (pintype "passive"))
      (node (ref "R17") (pin "1") (pinfunction "1_1") (pintype "passive"))
    )
    (net (code "24") (name "Net-(D3-ANODE)") (class "Default")
      (node (ref "D3") (pin "2") (pinfunction "ANODE_2") (pintype "passive"))
      (node (ref "U10") (pin "3") (pinfunction "D2_3") (pintype "passive"))
    )
    (net (code "25") (name "Net-(D3-CATHODE)") (class "Default")
      (node (ref "D3") (pin "1") (pinfunction "CATHODE_1") (pintype "passive"))
      (node (ref "R18") (pin "1") (pinfunction "1_1") (pintype "passive"))
    )
    (net (code "26") (name "Net-(D6-Anode)") (class "Default")
      (node (ref "D6") (pin "2") (pinfunction "Anode_2") (pintype "passive"))
      (node (ref "D7") (pin "2") (pinfunction "CATHODE_2") (pintype "passive"))
      (node (ref "J3") (pin "3") (pinfunction "3_3") (pintype "passive"))
    )
    (net (code "27") (name "Net-(D8-ANODE)") (class "Default")
      (node (ref "D8") (pin "2") (pinfunction "ANODE_2") (pintype "passive"))
      (node (ref "U9") (pin "6") (pinfunction "D1_6") (pintype "passive"))
    )
    (net (code "28") (name "Net-(D8-CATHODE)") (class "Default")
      (node (ref "D8") (pin "1") (pinfunction "CATHODE_1") (pintype "passive"))
      (node (ref "R23") (pin "1") (pinfunction "1_1") (pintype "passive"))
    )
    (net (code "29") (name "Net-(D9-ANODE)") (class "Default")
      (node (ref "D9") (pin "2") (pinfunction "ANODE_2") (pintype "passive"))
      (node (ref "U9") (pin "3") (pinfunction "D2_3") (pintype "passive"))
    )
    (net (code "30") (name "Net-(D9-CATHODE)") (class "Default")
      (node (ref "D9") (pin "1") (pinfunction "CATHODE_1") (pintype "passive"))
      (node (ref "R24") (pin "1") (pinfunction "1_1") (pintype "passive"))
    )
    (net (code "31") (name "Net-(D15-CATHODE)") (class "Default")
      (node (ref "D15") (pin "2") (pinfunction "CATHODE_2") (pintype "passive"))
      (node (ref "J1") (pin "7") (pinfunction "7_7") (pintype "passive"))
      (node (ref "R6") (pin "1") (pinfunction "1_1") (pintype "passive"))
    )
    (net (code "32") (name "Net-(U1-VCAP)") (class "Default")
      (node (ref "C3") (pin "1") (pinfunction "1_1") (pintype "passive"))
      (node (ref "U1") (pin "8") (pinfunction "VCAP_8") (pintype "passive"))
    )
    (net (code "33") (name "Net-(U2-VDEC1)") (class "Default")
      (node (ref "C8") (pin "2") (pinfunction "2_2") (pintype "passive"))
      (node (ref "C9") (pin "2") (pinfunction "2_2") (pintype "passive"))
      (node (ref "U2") (pin "1") (pinfunction "VDEC1_1") (pintype "passive"))
      (node (ref "U2") (pin "9") (pinfunction "VDEC2_9") (pintype "passive"))
    )
    (net (code "34") (name "Net-(U8-BDS)") (class "Default")
      (node (ref "C16") (pin "1") (pinfunction "1_1") (pintype "passive"))
      (node (ref "U8") (pin "5") (pinfunction "BDS_5") (pintype "passive"))
    )
    (net (code "35") (name "Net-(U8-COMP)") (class "Default")
      (node (ref "C13") (pin "1") (pinfunction "1_1") (pintype "passive"))
      (node (ref "C24") (pin "1") (pinfunction "1_1") (pintype "passive"))
      (node (ref "U8") (pin "3") (pinfunction "COMP_3") (pintype "passive"))
    )
    (net (code "36") (name "Net-(U8-EN)") (class "Default")
      (node (ref "R15") (pin "1") (pinfunction "1_1") (pintype "passive"))
      (node (ref "U8") (pin "7") (pinfunction "EN_7") (pintype "passive"))
    )
    (net (code "37") (name "Net-(U8-FB)") (class "Default")
      (node (ref "C14") (pin "2") (pinfunction "2_2") (pintype "passive"))
      (node (ref "C19") (pin "2") (pinfunction "2_2") (pintype "passive"))
      (node (ref "FB1") (pin "1") (pinfunction "1_1") (pintype "passive"))
      (node (ref "L1") (pin "2") (pinfunction "2_2") (pintype "passive"))
      (node (ref "U8") (pin "4") (pinfunction "FB_4") (pintype "passive"))
    )
    (net (code "38") (name "VCC_5V") (class "Default")
      (node (ref "5V") (pin "1") (pinfunction "1_1") (pintype "passive"))
      (node (ref "C1") (pin "1") (pinfunction "1_1") (pintype "passive"))
      (node (ref "C15") (pin "1") (pinfunction "1_1") (pintype "passive"))
      (node (ref "C2") (pin "2") (pinfunction "2_2") (pintype "passive"))
      (node (ref "C25") (pin "1") (pinfunction "1_1") (pintype "passive"))
      (node (ref "C26") (pin "1") (pinfunction "1_1") (pintype "passive"))
      (node (ref "C4") (pin "1") (pinfunction "1_1") (pintype "passive"))
      (node (ref "C5") (pin "1") (pinfunction "1_1") (pintype "passive"))
      (node (ref "C7") (pin "2") (pinfunction "2_2") (pintype "passive"))
      (node (ref "FB1") (pin "2") (pinfunction "2_2") (pintype "passive"))
      (node (ref "J1") (pin "1") (pinfunction "1_1") (pintype "passive"))
      (node (ref "J1") (pin "2") (pinfunction "2_2") (pintype "passive"))
      (node (ref "R1") (pin "2") (pinfunction "2_2") (pintype "passive"))
      (node (ref "R5") (pin "2") (pinfunction "2_2") (pintype "passive"))
      (node (ref "U1") (pin "9") (pinfunction "VDD_9") (pintype "passive"))
      (node (ref "U10") (pin "1") (pinfunction "S1_1") (pintype "passive"))
      (node (ref "U10") (pin "4") (pinfunction "S2_4") (pintype "passive"))
      (node (ref "U2") (pin "11") (pinfunction "VDD2_11") (pintype "passive"))
      (node (ref "U2") (pin "3") (pinfunction "VDD1_3") (pintype "passive"))
      (node (ref "U9") (pin "1") (pinfunction "S1_1") (pintype "passive"))
      (node (ref "U9") (pin "4") (pinfunction "S2_4") (pintype "passive"))
    )
    (net (code "39") (name "VCC_IN") (class "Default")
      (node (ref "C11") (pin "2") (pinfunction "2_2") (pintype "passive"))
      (node (ref "C12") (pin "1") (pinfunction "1_1") (pintype "passive"))
      (node (ref "C18") (pin "1") (pinfunction "1_1") (pintype "passive"))
      (node (ref "D6") (pin "1") (pinfunction "Cathode_1") (pintype "passive"))
      (node (ref "R15") (pin "2") (pinfunction "2_2") (pintype "passive"))
      (node (ref "U8") (pin "8") (pinfunction "VS_8") (pintype "passive"))
      (node (ref "VCC_IN") (pin "1") (pinfunction "1_1") (pintype "passive"))
    )
    (net (code "40") (name "unconnected-(FID1-Pad0)") (class "Default")
      (node (ref "FID1") (pin "0") (pinfunction "0_0") (pintype "passive+no_connect"))
    )
    (net (code "41") (name "unconnected-(FID2-Pad0)") (class "Default")
      (node (ref "FID2") (pin "0") (pinfunction "0_0") (pintype "passive+no_connect"))
    )
    (net (code "42") (name "unconnected-(FID3-Pad0)") (class "Default")
      (node (ref "FID3") (pin "0") (pinfunction "0_0") (pintype "passive+no_connect"))
    )
    (net (code "43") (name "unconnected-(FID4-Pad0)") (class "Default")
      (node (ref "FID4") (pin "0") (pinfunction "0_0") (pintype "passive+no_connect"))
    )
    (net (code "44") (name "unconnected-(U1-PA2{slash}OSCOUT-Pad6)") (class "Default")
      (node (ref "U1") (pin "6") (pinfunction "PA2/OSCOUT_6") (pintype "passive+no_connect"))
    )
    (net (code "45") (name "unconnected-(U1-PB4_(T){slash}I2C_SCL_[ADC_ETR]-Pad12)") (class "Default")
      (node (ref "U1") (pin "12") (pinfunction "PB4_(T)/I2C_SCL_[ADC_ETR]_12") (pintype "passive+no_connect"))
    )
    (net (code "46") (name "unconnected-(U1-PB5_(T){slash}I2C_SDA_[TIM1_BKIN]-Pad11)") (class "Default")
      (node (ref "U1") (pin "11") (pinfunction "PB5_(T)/I2C_SDA_[TIM1_BKIN]_11") (pintype "passive+no_connect"))
    )
  )
)
